# LED.net
KiCad netlist of a schematic drawn in Altium Designer
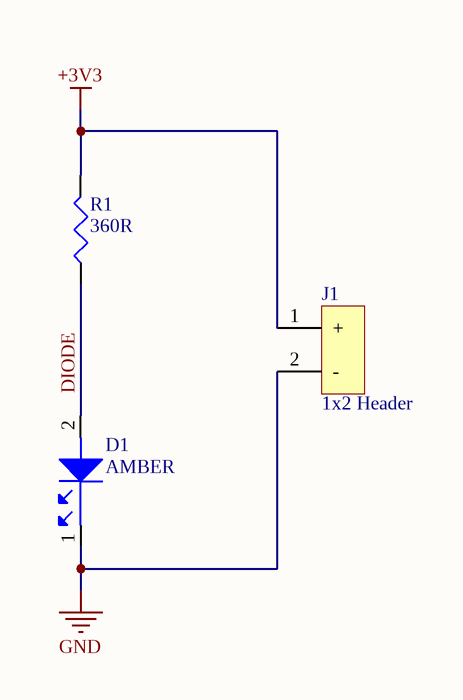
[diagram p0: LED.SchDoc]

(export (version "E")
  (design (tool "Eeschema 10.0.6"))
  (components
    (comp (ref "D1")
      (value "AMBER")
      (footprint "LED0603AMBER")
      (description "PANASONIC - LNJ437W84RA - LED, AMBER, 0.8MM X 1.1MM, 25MCD, 590NM")
      (fields
        (field (name "MANUFACTURER") "Panasonic SSG")
        (field (name "MANUFACTURER PART NUMBER") "LNJ437W84RA")
      )
      (libsource (lib "LED_SchLib") (part "LNJ437W84RA"))
    )
    (comp (ref "J1")
      (value "1x2 Header")
      (footprint "HEADER1x2")
      (description "Conn Wire to Board HDR 2 POS 2.54mm Solder ST Thru-Hole Bag")
      (fields (field (name "MANUFACTURER") "Molex") (field (name "MANUFACTURER PART NUMBER") "22-29-2021"))
      (libsource (lib "LED_SchLib") (part "22-29-2021"))
    )
    (comp (ref "R1")
      (value "360R")
      (footprint "R0805")
      (fields
        (field (name "MANUFACTURER") "Vishay")
        (field (name "MANUFACTURER PART NUMBER") "CRCW080536R0FKEA")
        (field (name "TOLERANCE") "1%")
      )
      (libsource (lib "LED_SchLib") (part "CRCW080536R0FKEA"))
    )
  )
  (nets
    (net (code "1") (name "+3V3") (class "Default")
      (node (ref "J1") (pin "1") (pinfunction "+_1") (pintype "passive"))
      (node (ref "R1") (pin "2") (pinfunction "2_2") (pintype "passive"))
    )
    (net (code "2") (name "/DIODE") (class "Default")
      (node (ref "D1") (pin "2") (pinfunction "2_2") (pintype "passive"))
      (node (ref "R1") (pin "1") (pinfunction "1_1") (pintype "passive"))
    )
    (net (code "3") (name "GND") (class "Default")
      (node (ref "D1") (pin "1") (pinfunction "1_1") (pintype "passive"))
      (node (ref "J1") (pin "2") (pinfunction "-_2") (pintype "passive"))
    )
  )
)
